# WheatstoneBridge.net
KiCad netlist of a schematic drawn in Altium Designer
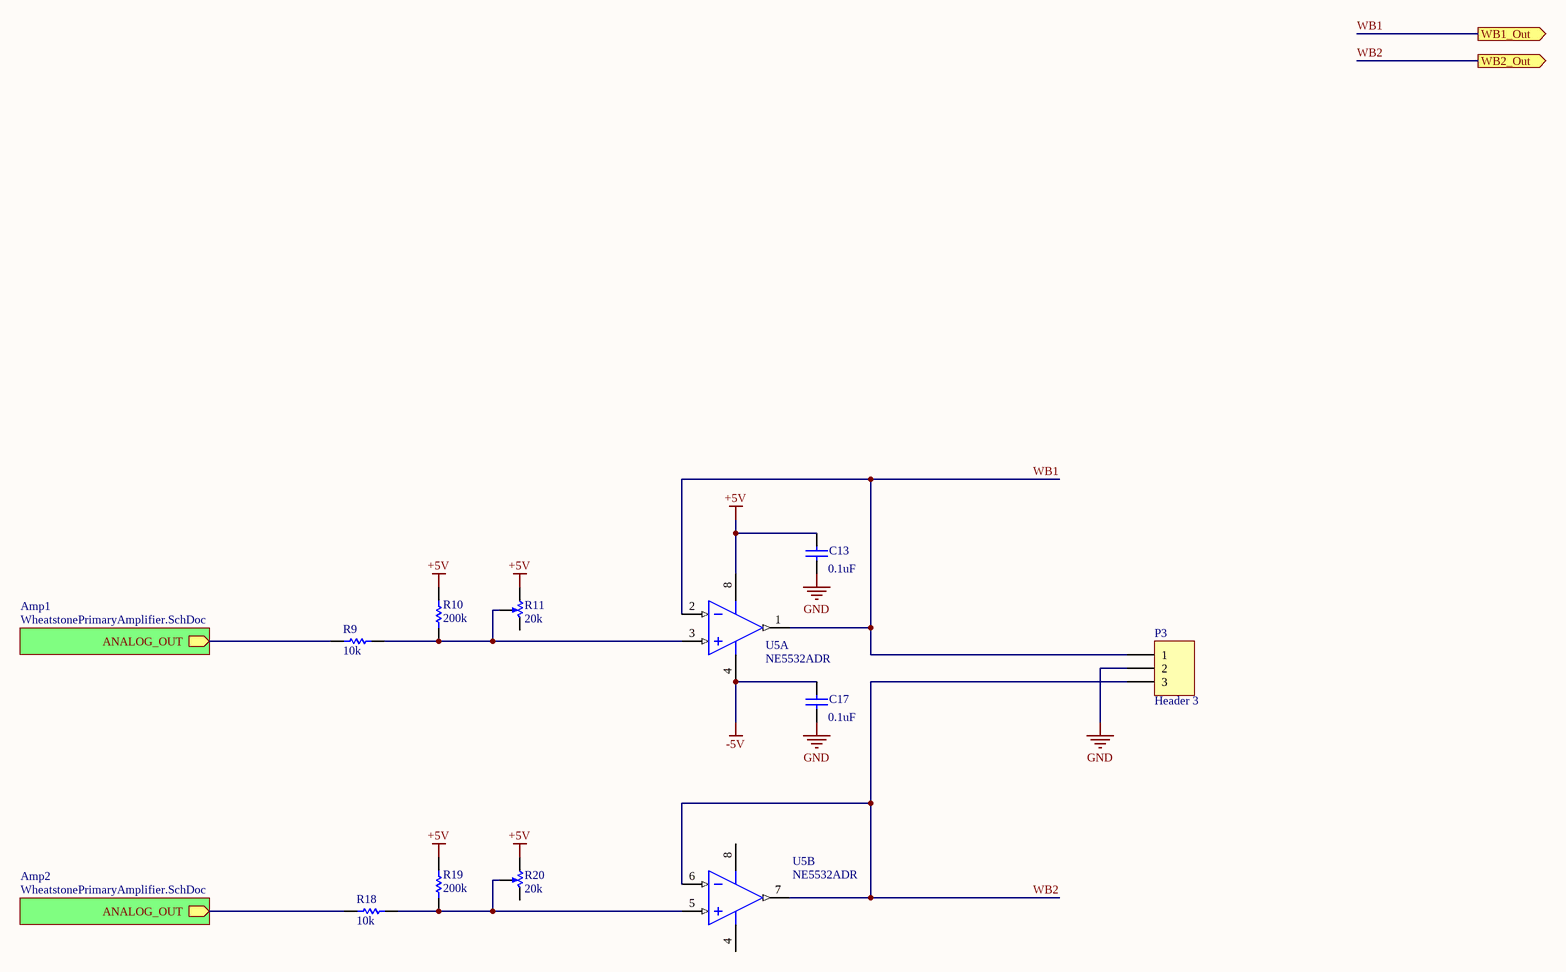
[diagram p0: WheatstoneBridge.SchDoc]

(export (version "E")
  (design (tool "Eeschema 10.0.6"))
  (components
    (comp (ref "C13")
      (value "0.1uF")
      (footprint "1608[0603]")
      (description "Capacitor (Semiconductor SIM Model)")
      (fields (field (name "Comment") "Cap Semi") (field (name "PUBLISHER") "Altium Limited"))
      (libsource (lib "Miscellaneous Devices") (part "Cap Semi"))
    )
    (comp (ref "C17")
      (value "0.1uF")
      (footprint "1608[0603]")
      (description "Capacitor (Semiconductor SIM Model)")
      (fields (field (name "Comment") "Cap Semi") (field (name "PUBLISHER") "Altium Limited"))
      (libsource (lib "Miscellaneous Devices") (part "Cap Semi"))
    )
    (comp (ref "P3")
      (value "Header 3")
      (footprint "HDR1X3")
      (description "Header, 3-Pin")
      (fields (field (name "PUBLISHER") "Altium Limited"))
      (libsource (lib "Miscellaneous Connectors") (part "Header 3"))
    )
    (comp (ref "R9")
      (value "10k")
      (footprint "RESC1608X55X25ML10T15")
      (description "Chip Resistor, 1 KOhm, +/-1%, 0.1 W, -55 to 155 degC, 0603 (1608 Metric), RoHS, Tape and Reel")
      (libsource (lib "Altium Content Vault") (part "RES-2"))
    )
    (comp (ref "R10")
      (value "200k")
      (footprint "RESC1608X55X25ML10T15")
      (description "Chip Resistor, 1 KOhm, +/-1%, 0.1 W, -55 to 155 degC, 0603 (1608 Metric), RoHS, Tape and Reel")
      (libsource (lib "Altium Content Vault") (part "RES-2"))
    )
    (comp (ref "R11")
      (value "20k")
      (footprint "PcbLib1:Trimpot_Cut_tape_3.4x3.4x2")
      (libsource (lib "Schlib1") (part "Component_1"))
    )
    (comp (ref "R18")
      (value "10k")
      (footprint "RESC1608X55X25ML10T15")
      (description "Chip Resistor, 1 KOhm, +/-1%, 0.1 W, -55 to 155 degC, 0603 (1608 Metric), RoHS, Tape and Reel")
      (libsource (lib "Altium Content Vault") (part "RES-2"))
    )
    (comp (ref "R19")
      (value "200k")
      (footprint "RESC1608X55X25ML10T15")
      (description "Chip Resistor, 1 KOhm, +/-1%, 0.1 W, -55 to 155 degC, 0603 (1608 Metric), RoHS, Tape and Reel")
      (libsource (lib "Altium Content Vault") (part "RES-2"))
    )
    (comp (ref "R20")
      (value "20k")
      (footprint "PcbLib1:Trimpot_Cut_tape_3.4x3.4x2")
      (libsource (lib "Schlib1") (part "Component_1"))
    )
    (comp (ref "U5")
      (value "NE5532ADR")
      (footprint "D0008A_M")
      (fields (field (name "MANUFACTURER") "Texas Instruments"))
      (libsource (lib "Altium Content Vault") (part "TI-AMP-D6-2-8_D"))
    )
  )
  (nets
    (net (code "1") (name "+5V") (class "Default")
      (node (ref "C13") (pin "1") (pinfunction "1_1") (pintype "passive"))
      (node (ref "R10") (pin "1") (pinfunction "1_1") (pintype "passive"))
      (node (ref "R11") (pin "1") (pinfunction "1_1") (pintype "passive"))
      (node (ref "R19") (pin "1") (pinfunction "1_1") (pintype "passive"))
      (node (ref "R20") (pin "1") (pinfunction "1_1") (pintype "passive"))
      (node (ref "U5") (pin "8") (pinfunction "VCC+_8") (pintype "power_in"))
    )
    (net (code "2") (name "-5V") (class "Default")
      (node (ref "C17") (pin "1") (pinfunction "1_1") (pintype "passive"))
      (node (ref "U5") (pin "4") (pinfunction "VCC-_4") (pintype "power_in"))
    )
    (net (code "3") (name "/ANALOG_OUT") (class "Default")
      (node (ref "R9") (pin "2") (pinfunction "2_2") (pintype "passive"))
    )
    (net (code "4") (name "/ANALOG_OUT_1") (class "Default")
      (node (ref "R18") (pin "2") (pinfunction "2_2") (pintype "passive"))
    )
    (net (code "5") (name "/WB1") (class "Default")
      (node (ref "P3") (pin "1") (pinfunction "1_1") (pintype "passive"))
      (node (ref "U5") (pin "1") (pinfunction "OUT1_1") (pintype "output"))
      (node (ref "U5") (pin "2") (pinfunction "IN1-_2") (pintype "input"))
    )
    (net (code "6") (name "/WB2") (class "Default")
      (node (ref "P3") (pin "3") (pinfunction "3_3") (pintype "passive"))
      (node (ref "U5") (pin "6") (pinfunction "IN2-_6") (pintype "input"))
      (node (ref "U5") (pin "7") (pinfunction "OUT2_7") (pintype "output"))
    )
    (net (code "7") (name "GND") (class "Default")
      (node (ref "C13") (pin "2") (pinfunction "2_2") (pintype "passive"))
      (node (ref "C17") (pin "2") (pinfunction "2_2") (pintype "passive"))
      (node (ref "P3") (pin "2") (pinfunction "2_2") (pintype "passive"))
    )
    (net (code "8") (name "Net-(U5A-IN1+)") (class "Default")
      (node (ref "R10") (pin "2") (pinfunction "2_2") (pintype "passive"))
      (node (ref "R11") (pin "2") (pinfunction "2_2") (pintype "passive"))
      (node (ref "R9") (pin "1") (pinfunction "1_1") (pintype "passive"))
      (node (ref "U5") (pin "3") (pinfunction "IN1+_3") (pintype "input"))
    )
    (net (code "9") (name "Net-(U5B-IN2+)") (class "Default")
      (node (ref "R18") (pin "1") (pinfunction "1_1") (pintype "passive"))
      (node (ref "R19") (pin "2") (pinfunction "2_2") (pintype "passive"))
      (node (ref "R20") (pin "2") (pinfunction "2_2") (pintype "passive"))
      (node (ref "U5") (pin "5") (pinfunction "IN2+_5") (pintype "input"))
    )
    (net (code "10") (name "unconnected-(R11-Pad3)") (class "Default")
      (node (ref "R11") (pin "3") (pinfunction "3_3") (pintype "passive"))
    )
    (net (code "11") (name "unconnected-(R20-Pad3)") (class "Default")
      (node (ref "R20") (pin "3") (pinfunction "3_3") (pintype "passive"))
    )
    (net (code "12") (name "unconnected-(U5B-VCC+-Pad8)") (class "Default")
      (node (ref "U5") (pin "8") (pinfunction "VCC+_8") (pintype "power_in"))
    )
    (net (code "13") (name "unconnected-(U5B-VCC--Pad4)") (class "Default")
      (node (ref "U5") (pin "4") (pinfunction "VCC-_4") (pintype "power_in"))
    )
  )
)
